# power.net
KiCad netlist of a schematic drawn in Altium Designer
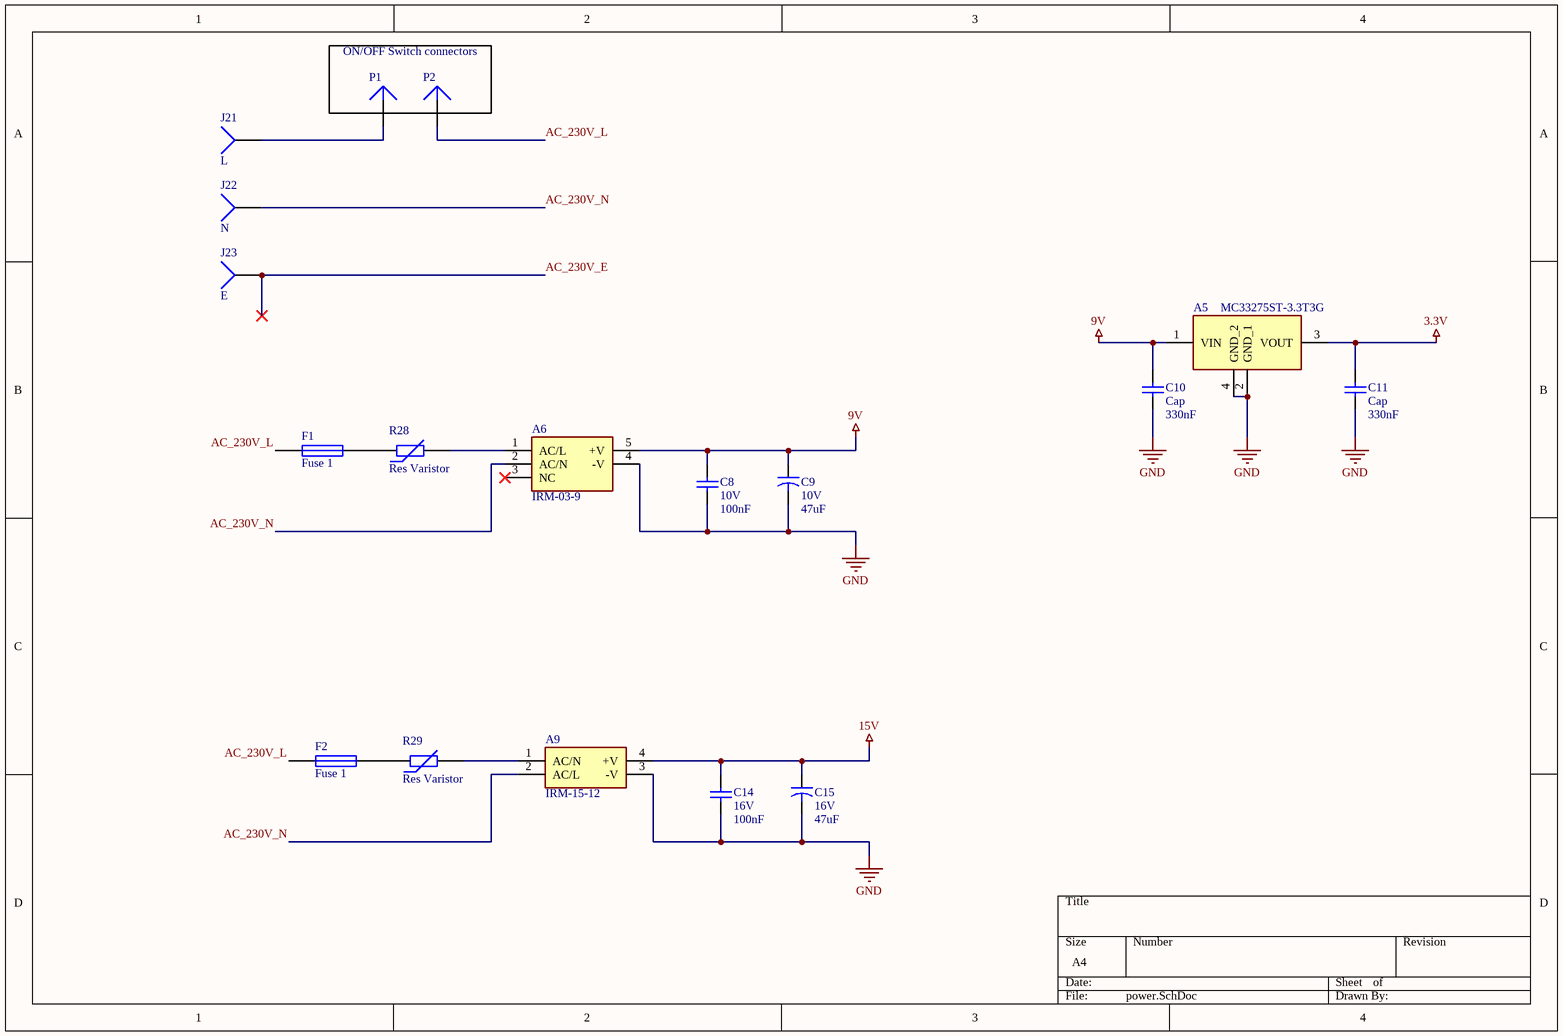
[diagram p0: power.SchDoc]

(export (version "E")
  (design (tool "Eeschema 10.0.6"))
  (components
    (comp (ref "A5")
      (value "MC33275ST-3.3T3G")
      (footprint "SOT230P700X175-4N")
      (description "Integrated Circuit")
      (fields
        (field (name "MOUSER PART NUMBER") "863-MC33275ST-3.3T3G")
        (field (name "RS PART NUMBER") "7856910P")
      )
      (libsource (lib "ALL") (part "MC33275ST-3.3T3G"))
    )
    (comp (ref "A6")
      (value "IRM-03-9")
      (footprint "IRM039")
      (description "Power Supply")
      (fields (field (name "MOUSER PART NUMBER") "709-IRM03-9") (field (name "RS PART NUMBER") "1359235P"))
      (libsource (lib "SamacSys2") (part "IRM-03-9"))
    )
    (comp (ref "A9")
      (value "IRM-15-12")
      (footprint "IRM-15-12")
      (description "Power Supply")
      (fields (field (name "MOUSER2 PART NUMBER") "709-IRM15-12"))
      (libsource (lib "SamacSys2") (part "IRM-15-12"))
    )
    (comp (ref "C8")
      (value "10V")
      (footprint "6-0805_L")
      (description "Capacitor")
      (fields (field (name "ALTIUM_VALUE") "100nF") (field (name "PUBLISHER") "Altium Limited"))
      (libsource (lib "Miscellaneous Devices") (part "Cap"))
    )
    (comp (ref "C9")
      (value "10V")
      (footprint "CAPAE830X1050N")
      (description "Capacitor")
      (fields (field (name "ALTIUM_VALUE") "47uF") (field (name "PUBLISHER") "Altium Limited"))
      (libsource (lib "Miscellaneous Devices") (part "Cap2"))
    )
    (comp (ref "C10")
      (value "Cap")
      (footprint "6-0805_L")
      (description "Capacitor")
      (fields (field (name "ALTIUM_VALUE") "330nF") (field (name "PUBLISHER") "Altium Limited"))
      (libsource (lib "Miscellaneous Devices") (part "Cap"))
    )
    (comp (ref "C11")
      (value "Cap")
      (footprint "6-0805_L")
      (description "Capacitor")
      (fields (field (name "ALTIUM_VALUE") "330nF") (field (name "PUBLISHER") "Altium Limited"))
      (libsource (lib "Miscellaneous Devices") (part "Cap"))
    )
    (comp (ref "C14")
      (value "16V")
      (footprint "6-0805_L")
      (description "Capacitor")
      (fields (field (name "ALTIUM_VALUE") "100nF") (field (name "PUBLISHER") "Altium Limited"))
      (libsource (lib "Miscellaneous Devices") (part "Cap"))
    )
    (comp (ref "C15")
      (value "16V")
      (footprint "CAPAE830X1050N")
      (description "Capacitor")
      (fields (field (name "ALTIUM_VALUE") "47uF") (field (name "PUBLISHER") "Altium Limited"))
      (libsource (lib "Miscellaneous Devices") (part "Cap2"))
    )
    (comp (ref "F1")
      (value "Fuse 1")
      (footprint "0751.0056")
      (description "Fuse")
      (fields (field (name "PUBLISHER") "Altium Limited"))
      (libsource (lib "Miscellaneous Devices") (part "Fuse 1"))
    )
    (comp (ref "F2")
      (value "Fuse 1")
      (footprint "0751.0056")
      (description "Fuse")
      (fields (field (name "PUBLISHER") "Altium Limited"))
      (libsource (lib "Miscellaneous Devices") (part "Fuse 1"))
    )
    (comp (ref "J21")
      (value "L")
      (footprint "PIN1")
      (description "Socket")
      (fields (field (name "PUBLISHER") "Altium Limited"))
      (libsource (lib "Miscellaneous Connectors") (part "Socket"))
    )
    (comp (ref "J22")
      (value "N")
      (footprint "PIN1")
      (description "Socket")
      (fields (field (name "PUBLISHER") "Altium Limited"))
      (libsource (lib "Miscellaneous Connectors") (part "Socket"))
    )
    (comp (ref "J23")
      (value "E")
      (footprint "PIN1")
      (description "Socket")
      (fields (field (name "PUBLISHER") "Altium Limited"))
      (libsource (lib "Miscellaneous Connectors") (part "Socket"))
    )
    (comp (ref "P1")
      (value "Plug")
      (footprint "PIN1")
      (fields (field (name "PUBLISHER") "Altium Limited"))
      (libsource (lib "Miscellaneous Connectors") (part "Plug"))
    )
    (comp (ref "P2")
      (value "Plug")
      (footprint "PIN1")
      (fields (field (name "PUBLISHER") "Altium Limited"))
      (libsource (lib "Miscellaneous Connectors") (part "Plug"))
    )
    (comp (ref "R28")
      (value "Res Varistor")
      (footprint "CAPR5-4X5")
      (description "Varistor (Voltage-Sensitive Resistor)")
      (fields (field (name "PUBLISHER") "Altium Limited"))
      (libsource (lib "Miscellaneous Devices") (part "Res Varistor"))
    )
    (comp (ref "R29")
      (value "Res Varistor")
      (footprint "CAPR5-4X5")
      (description "Varistor (Voltage-Sensitive Resistor)")
      (fields (field (name "PUBLISHER") "Altium Limited"))
      (libsource (lib "Miscellaneous Devices") (part "Res Varistor"))
    )
  )
  (nets
    (net (code "1") (name "/AC_230V_E") (class "Default")
      (node (ref "J23") (pin "1") (pinfunction "1_1") (pintype "passive+no_connect"))
    )
    (net (code "2") (name "/AC_230V_L") (class "Default")
      (node (ref "F1") (pin "1") (pinfunction "1_1") (pintype "passive"))
      (node (ref "F2") (pin "1") (pinfunction "1_1") (pintype "passive"))
      (node (ref "P2") (pin "1") (pinfunction "1_1") (pintype "passive"))
    )
    (net (code "3") (name "/AC_230V_N") (class "Default")
      (node (ref "A6") (pin "2") (pinfunction "AC/N_2") (pintype "passive"))
      (node (ref "A9") (pin "2") (pinfunction "AC/L_2") (pintype "passive"))
      (node (ref "J22") (pin "1") (pinfunction "1_1") (pintype "passive"))
    )
    (net (code "4") (name "3.3V") (class "Default")
      (node (ref "A5") (pin "3") (pinfunction "VOUT_3") (pintype "passive"))
      (node (ref "C11") (pin "2") (pinfunction "2_2") (pintype "passive"))
    )
    (net (code "5") (name "9V") (class "Default")
      (node (ref "A5") (pin "1") (pinfunction "VIN_1") (pintype "passive"))
      (node (ref "A6") (pin "5") (pinfunction "+V_5") (pintype "passive"))
      (node (ref "C10") (pin "2") (pinfunction "2_2") (pintype "passive"))
      (node (ref "C8") (pin "2") (pinfunction "2_2") (pintype "passive"))
      (node (ref "C9") (pin "1") (pinfunction "1_1") (pintype "passive"))
    )
    (net (code "6") (name "15V") (class "Default")
      (node (ref "A9") (pin "4") (pinfunction "+V_4") (pintype "passive"))
      (node (ref "C14") (pin "2") (pinfunction "2_2") (pintype "passive"))
      (node (ref "C15") (pin "1") (pinfunction "1_1") (pintype "passive"))
    )
    (net (code "7") (name "GND") (class "Default")
      (node (ref "A5") (pin "2") (pinfunction "GND_1_2") (pintype "passive"))
      (node (ref "A5") (pin "4") (pinfunction "GND_2_4") (pintype "passive"))
      (node (ref "A6") (pin "4") (pinfunction "-V_4") (pintype "passive"))
      (node (ref "A9") (pin "3") (pinfunction "-V_3") (pintype "passive"))
      (node (ref "C10") (pin "1") (pinfunction "1_1") (pintype "passive"))
      (node (ref "C11") (pin "1") (pinfunction "1_1") (pintype "passive"))
      (node (ref "C14") (pin "1") (pinfunction "1_1") (pintype "passive"))
      (node (ref "C15") (pin "2") (pinfunction "2_2") (pintype "passive"))
      (node (ref "C8") (pin "1") (pinfunction "1_1") (pintype "passive"))
      (node (ref "C9") (pin "2") (pinfunction "2_2") (pintype "passive"))
    )
    (net (code "8") (name "Net-(A6-AC{slash}L)") (class "Default")
      (node (ref "A6") (pin "1") (pinfunction "AC/L_1") (pintype "passive"))
      (node (ref "R28") (pin "2") (pinfunction "2_2") (pintype "passive"))
    )
    (net (code "9") (name "Net-(A9-AC{slash}N)") (class "Default")
      (node (ref "A9") (pin "1") (pinfunction "AC/N_1") (pintype "passive"))
      (node (ref "R29") (pin "2") (pinfunction "2_2") (pintype "passive"))
    )
    (net (code "10") (name "Net-(F1-Pad2)") (class "Default")
      (node (ref "F1") (pin "2") (pinfunction "2_2") (pintype "passive"))
      (node (ref "R28") (pin "1") (pinfunction "1_1") (pintype "passive"))
    )
    (net (code "11") (name "Net-(F2-Pad2)") (class "Default")
      (node (ref "F2") (pin "2") (pinfunction "2_2") (pintype "passive"))
      (node (ref "R29") (pin "1") (pinfunction "1_1") (pintype "passive"))
    )
    (net (code "12") (name "Net-(J21-Pad1)") (class "Default")
      (node (ref "J21") (pin "1") (pinfunction "1_1") (pintype "passive"))
      (node (ref "P1") (pin "1") (pinfunction "1_1") (pintype "passive"))
    )
    (net (code "13") (name "unconnected-(A6-NC-Pad3)") (class "Default")
      (node (ref "A6") (pin "3") (pinfunction "NC_3") (pintype "passive+no_connect"))
    )
  )
)
